# dc-1.net
KiCad netlist of a schematic drawn in Altium Designer
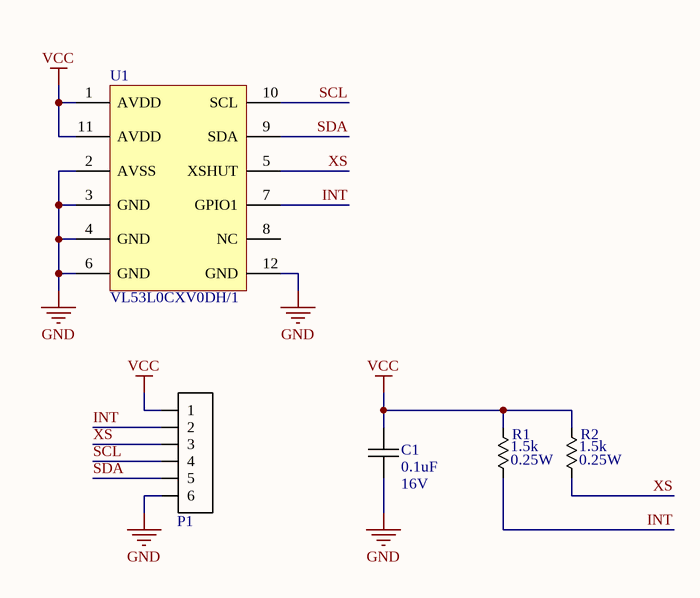
[diagram p0: dc-1.SchDoc]

(export (version "E")
  (design (tool "Eeschema 10.0.6"))
  (components
    (comp (ref "C1")
      (value "cap_single_np")
      (footprint "chip_0603")
      (description "CAP, 0.1uF, ±10%, 16V, X7R, 0603")
      (fields
        (field (name "TOLERANCE") "±10%")
        (field (name "CAPACITANCE") "0.1uF")
        (field (name "VOLTAGE RATING") "16V")
        (field (name "PART NUMBER") "CAP-00542")
      )
      (libsource (lib "Capacitors") (part "cap_single_np"))
    )
    (comp (ref "P1")
      (value "conn-6x1_0")
      (footprint "HDDR_6x1_RA")
      (description "Header, 6x1, 0.1\", Right-Angle")
      (fields (field (name "PART NUMBER") "CONN-00050") (field (name "MANUFACTURER") "Samtec"))
      (libsource (lib "Connectors") (part "conn-6x1_0"))
    )
    (comp (ref "R1")
      (value "res_single")
      (footprint "chip_0603")
      (description "RES SMD 1.5K OHM 1% 1/4W 0603")
      (fields
        (field (name "TOLERANCE") "1%")
        (field (name "RESISTANCE") "1.5k")
        (field (name "POWER RATING") "0.25W")
        (field (name "PART NUMBER") "RES-00284")
      )
      (libsource (lib "Resistors") (part "res_single"))
    )
    (comp (ref "R2")
      (value "res_single")
      (footprint "chip_0603")
      (description "RES SMD 1.5K OHM 1% 1/4W 0603")
      (fields
        (field (name "TOLERANCE") "1%")
        (field (name "RESISTANCE") "1.5k")
        (field (name "POWER RATING") "0.25W")
        (field (name "PART NUMBER") "RES-00284")
      )
      (libsource (lib "Resistors") (part "res_single"))
    )
    (comp (ref "U1")
      (value "VL53L0X")
      (footprint "VL53L0X")
      (description "Time-of-Flight Ranging Sensor, VL53L0X")
      (fields
        (field (name "MANUFACTURER PN") "VL53L0CXV0DH/1")
        (field (name "PART NUMBER") "MISC-00028")
        (field (name "MANUFACTURER") "ST")
      )
      (libsource (lib "Misc") (part "VL53L0X"))
    )
  )
  (nets
    (net (code "1") (name "/INT") (class "Default")
      (node (ref "P1") (pin "2") (pinfunction "2_2") (pintype "passive"))
      (node (ref "R1") (pin "2") (pinfunction "2_2") (pintype "passive"))
      (node (ref "U1") (pin "7") (pinfunction "GPIO1_7") (pintype "passive"))
    )
    (net (code "2") (name "/SCL") (class "Default")
      (node (ref "P1") (pin "4") (pinfunction "4_4") (pintype "passive"))
      (node (ref "U1") (pin "10") (pinfunction "SCL_10") (pintype "passive"))
    )
    (net (code "3") (name "/SDA") (class "Default")
      (node (ref "P1") (pin "5") (pinfunction "5_5") (pintype "passive"))
      (node (ref "U1") (pin "9") (pinfunction "SDA_9") (pintype "passive"))
    )
    (net (code "4") (name "/XS") (class "Default")
      (node (ref "P1") (pin "3") (pinfunction "3_3") (pintype "passive"))
      (node (ref "R2") (pin "2") (pinfunction "2_2") (pintype "passive"))
      (node (ref "U1") (pin "5") (pinfunction "XSHUT_5") (pintype "passive"))
    )
    (net (code "5") (name "GND") (class "Default")
      (node (ref "C1") (pin "2") (pinfunction "2_2") (pintype "passive"))
      (node (ref "P1") (pin "6") (pinfunction "6_6") (pintype "passive"))
      (node (ref "U1") (pin "12") (pinfunction "GND_12") (pintype "passive"))
      (node (ref "U1") (pin "2") (pinfunction "AVSS_2") (pintype "passive"))
      (node (ref "U1") (pin "3") (pinfunction "GND_3") (pintype "passive"))
      (node (ref "U1") (pin "4") (pinfunction "GND_4") (pintype "passive"))
      (node (ref "U1") (pin "6") (pinfunction "GND_6") (pintype "passive"))
    )
    (net (code "6") (name "VCC") (class "Default")
      (node (ref "C1") (pin "1") (pinfunction "1_1") (pintype "passive"))
      (node (ref "P1") (pin "1") (pinfunction "1_1") (pintype "passive"))
      (node (ref "R1") (pin "1") (pinfunction "1_1") (pintype "passive"))
      (node (ref "R2") (pin "1") (pinfunction "1_1") (pintype "passive"))
      (node (ref "U1") (pin "1") (pinfunction "AVDD_1") (pintype "passive"))
      (node (ref "U1") (pin "11") (pinfunction "AVDD_11") (pintype "passive"))
    )
    (net (code "7") (name "unconnected-(U1-NC-Pad8)") (class "Default")
      (node (ref "U1") (pin "8") (pinfunction "NC_8") (pintype "passive"))
    )
  )
)
